# dorbell.net
KiCad netlist of a schematic drawn in EAGLE
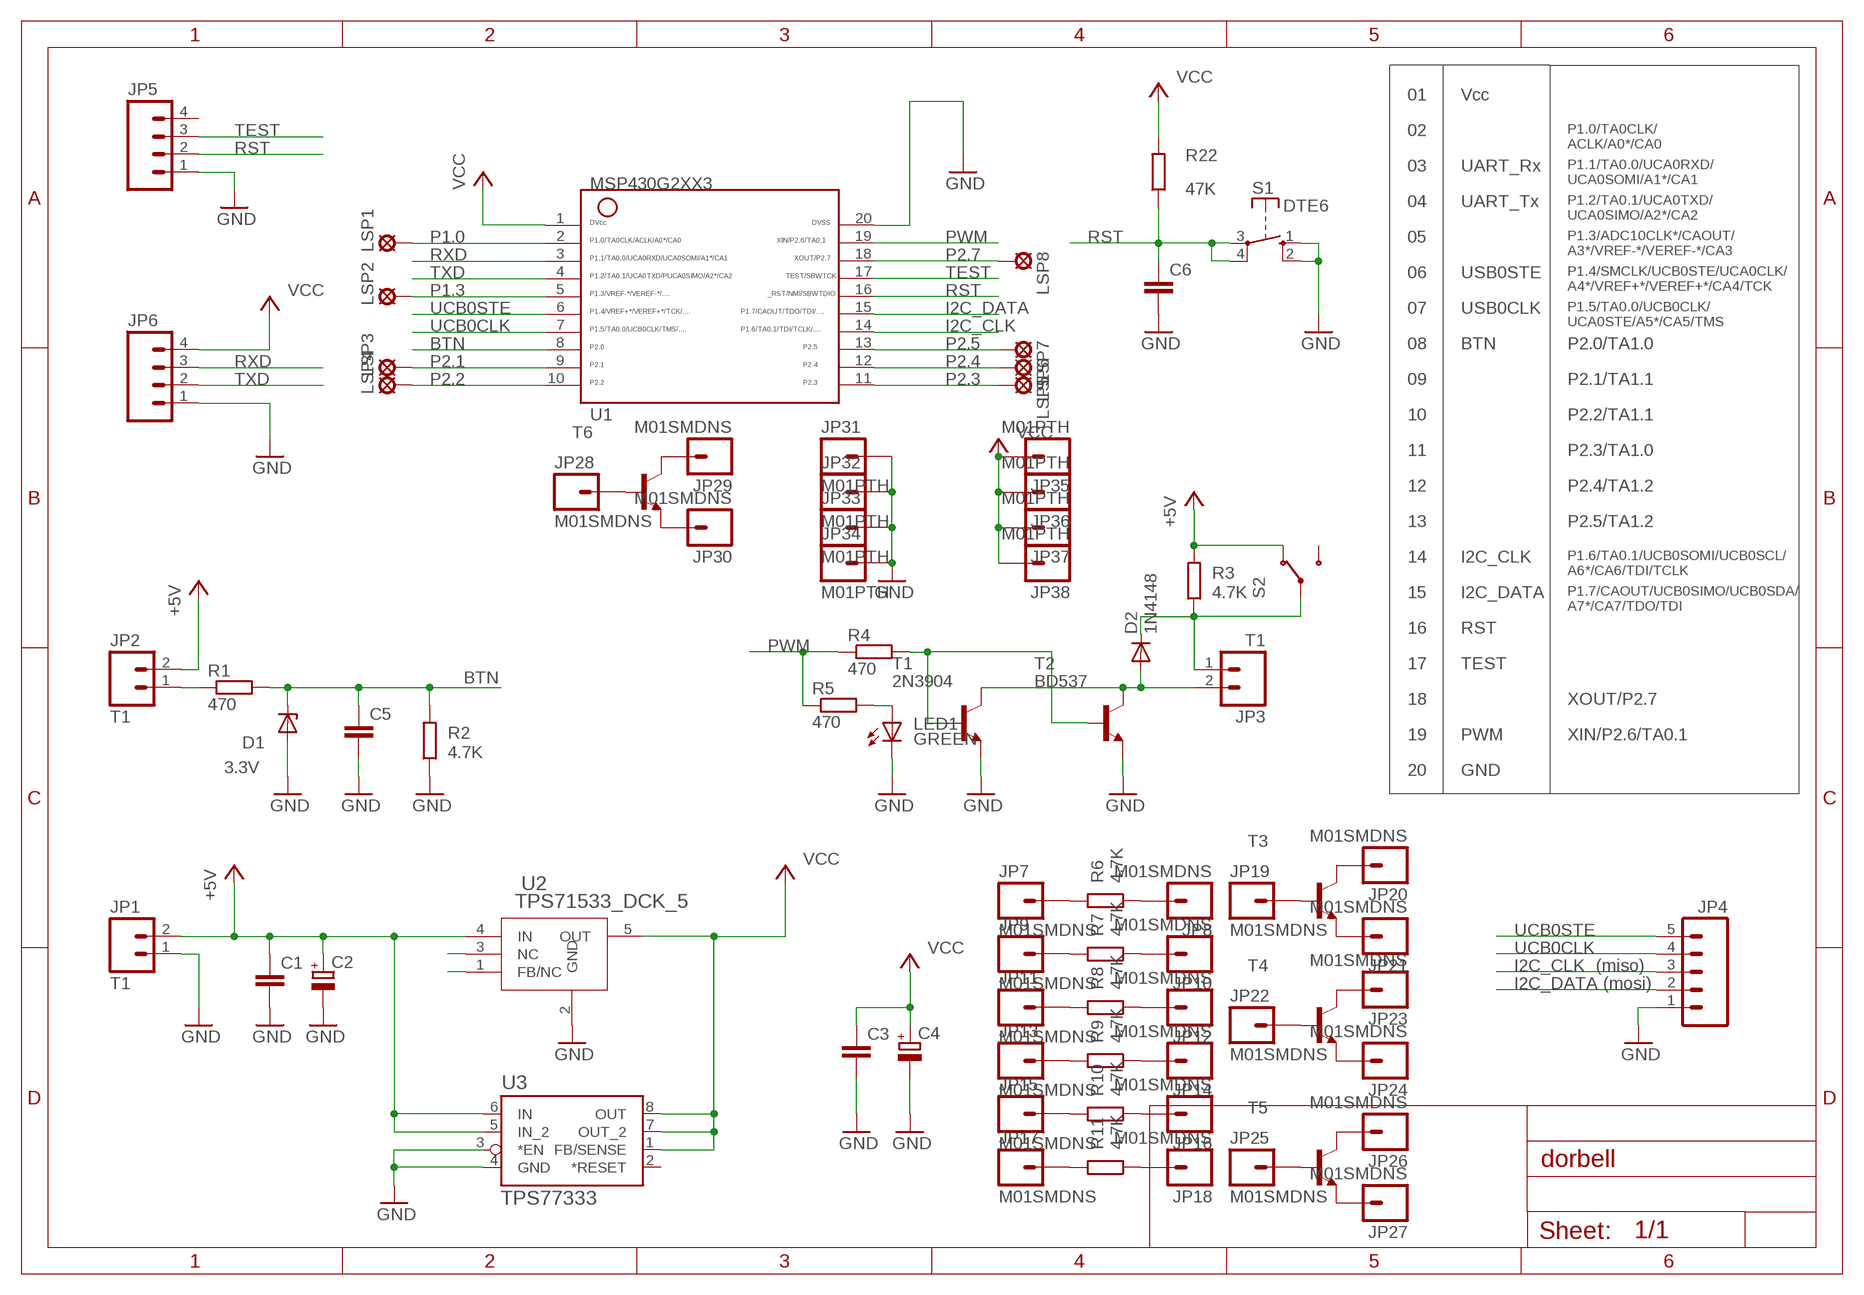
[diagram p0: schematic, sheet 1]

(export (version "E")
  (design (tool "Eeschema 10.0.6"))
  (components
    (comp (ref "C1")
      (value "C-EUC0805")
      (footprint "eagle-import:C0805")
      (libsource (lib "eagle-import") (part "C-EUC0805"))
    )
    (comp (ref "C2")
      (value "CPOL-EUE2.5-7")
      (footprint "eagle-import:E2,5-7")
      (libsource (lib "eagle-import") (part "CPOL-EUE2.5-7"))
    )
    (comp (ref "C3")
      (value "C-EUC0805")
      (footprint "eagle-import:C0805")
      (libsource (lib "eagle-import") (part "C-EUC0805"))
    )
    (comp (ref "C4")
      (value "CPOL-EUE2.5-7")
      (footprint "eagle-import:E2,5-7")
      (libsource (lib "eagle-import") (part "CPOL-EUE2.5-7"))
    )
    (comp (ref "C5")
      (value "C-EUC0805")
      (footprint "eagle-import:C0805")
      (libsource (lib "eagle-import") (part "C-EUC0805"))
    )
    (comp (ref "C6")
      (value "C-EUC0805")
      (footprint "eagle-import:C0805")
      (libsource (lib "eagle-import") (part "C-EUC0805"))
    )
    (comp (ref "D1")
      (value "3.3V")
      (footprint "eagle-import:ZDIO-2.5")
      (libsource (lib "eagle-import") (part "ZENER-DIODEZD-2.5"))
    )
    (comp (ref "D2")
      (value "1N4148")
      (footprint "eagle-import:SOD123")
      (libsource (lib "eagle-import") (part "DIODE-SOD123"))
    )
    (comp (ref "JP1")
      (value "T1")
      (footprint "eagle-import:SCREWTERMINAL-5MM-2")
      (libsource (lib "eagle-import") (part "M025MM"))
    )
    (comp (ref "JP2")
      (value "T1")
      (footprint "eagle-import:SCREWTERMINAL-5MM-2")
      (libsource (lib "eagle-import") (part "M025MM"))
    )
    (comp (ref "JP3")
      (value "T1")
      (footprint "eagle-import:SCREWTERMINAL-5MM-2")
      (libsource (lib "eagle-import") (part "M025MM"))
    )
    (comp (ref "JP4")
      (value "M05PTH")
      (footprint "eagle-import:1X05")
      (libsource (lib "eagle-import") (part "M05PTH"))
    )
    (comp (ref "JP5")
      (value "M04PTH")
      (footprint "eagle-import:1X04")
      (libsource (lib "eagle-import") (part "M04PTH"))
    )
    (comp (ref "JP6")
      (value "M04PTH")
      (footprint "eagle-import:1X04")
      (libsource (lib "eagle-import") (part "M04PTH"))
    )
    (comp (ref "JP7")
      (value "M01SMDNS")
      (footprint "eagle-import:1X01NS")
      (libsource (lib "eagle-import") (part "M01SMDNS"))
    )
    (comp (ref "JP8")
      (value "M01SMDNS")
      (footprint "eagle-import:1X01NS")
      (libsource (lib "eagle-import") (part "M01SMDNS"))
    )
    (comp (ref "JP9")
      (value "M01SMDNS")
      (footprint "eagle-import:1X01NS")
      (libsource (lib "eagle-import") (part "M01SMDNS"))
    )
    (comp (ref "JP10")
      (value "M01SMDNS")
      (footprint "eagle-import:1X01NS")
      (libsource (lib "eagle-import") (part "M01SMDNS"))
    )
    (comp (ref "JP11")
      (value "M01SMDNS")
      (footprint "eagle-import:1X01NS")
      (libsource (lib "eagle-import") (part "M01SMDNS"))
    )
    (comp (ref "JP12")
      (value "M01SMDNS")
      (footprint "eagle-import:1X01NS")
      (libsource (lib "eagle-import") (part "M01SMDNS"))
    )
    (comp (ref "JP13")
      (value "M01SMDNS")
      (footprint "eagle-import:1X01NS")
      (libsource (lib "eagle-import") (part "M01SMDNS"))
    )
    (comp (ref "JP14")
      (value "M01SMDNS")
      (footprint "eagle-import:1X01NS")
      (libsource (lib "eagle-import") (part "M01SMDNS"))
    )
    (comp (ref "JP15")
      (value "M01SMDNS")
      (footprint "eagle-import:1X01NS")
      (libsource (lib "eagle-import") (part "M01SMDNS"))
    )
    (comp (ref "JP16")
      (value "M01SMDNS")
      (footprint "eagle-import:1X01NS")
      (libsource (lib "eagle-import") (part "M01SMDNS"))
    )
    (comp (ref "JP17")
      (value "M01SMDNS")
      (footprint "eagle-import:1X01NS")
      (libsource (lib "eagle-import") (part "M01SMDNS"))
    )
    (comp (ref "JP18")
      (value "M01SMDNS")
      (footprint "eagle-import:1X01NS")
      (libsource (lib "eagle-import") (part "M01SMDNS"))
    )
    (comp (ref "JP19")
      (value "M01SMDNS")
      (footprint "eagle-import:1X01NS")
      (libsource (lib "eagle-import") (part "M01SMDNS"))
    )
    (comp (ref "JP20")
      (value "M01SMDNS")
      (footprint "eagle-import:1X01NS")
      (libsource (lib "eagle-import") (part "M01SMDNS"))
    )
    (comp (ref "JP21")
      (value "M01SMDNS")
      (footprint "eagle-import:1X01NS")
      (libsource (lib "eagle-import") (part "M01SMDNS"))
    )
    (comp (ref "JP22")
      (value "M01SMDNS")
      (footprint "eagle-import:1X01NS")
      (libsource (lib "eagle-import") (part "M01SMDNS"))
    )
    (comp (ref "JP23")
      (value "M01SMDNS")
      (footprint "eagle-import:1X01NS")
      (libsource (lib "eagle-import") (part "M01SMDNS"))
    )
    (comp (ref "JP24")
      (value "M01SMDNS")
      (footprint "eagle-import:1X01NS")
      (libsource (lib "eagle-import") (part "M01SMDNS"))
    )
    (comp (ref "JP25")
      (value "M01SMDNS")
      (footprint "eagle-import:1X01NS")
      (libsource (lib "eagle-import") (part "M01SMDNS"))
    )
    (comp (ref "JP26")
      (value "M01SMDNS")
      (footprint "eagle-import:1X01NS")
      (libsource (lib "eagle-import") (part "M01SMDNS"))
    )
    (comp (ref "JP27")
      (value "M01SMDNS")
      (footprint "eagle-import:1X01NS")
      (libsource (lib "eagle-import") (part "M01SMDNS"))
    )
    (comp (ref "JP28")
      (value "M01SMDNS")
      (footprint "eagle-import:1X01NS")
      (libsource (lib "eagle-import") (part "M01SMDNS"))
    )
    (comp (ref "JP29")
      (value "M01SMDNS")
      (footprint "eagle-import:1X01NS")
      (libsource (lib "eagle-import") (part "M01SMDNS"))
    )
    (comp (ref "JP30")
      (value "M01SMDNS")
      (footprint "eagle-import:1X01NS")
      (libsource (lib "eagle-import") (part "M01SMDNS"))
    )
    (comp (ref "JP31")
      (value "M01PTH")
      (footprint "eagle-import:1X01")
      (libsource (lib "eagle-import") (part "SparkFun-Connectors_M01PTH"))
    )
    (comp (ref "JP32")
      (value "M01PTH")
      (footprint "eagle-import:1X01")
      (libsource (lib "eagle-import") (part "SparkFun-Connectors_M01PTH"))
    )
    (comp (ref "JP33")
      (value "M01PTH")
      (footprint "eagle-import:1X01")
      (libsource (lib "eagle-import") (part "SparkFun-Connectors_M01PTH"))
    )
    (comp (ref "JP34")
      (value "M01PTH")
      (footprint "eagle-import:1X01")
      (libsource (lib "eagle-import") (part "SparkFun-Connectors_M01PTH"))
    )
    (comp (ref "JP35")
      (value "M01PTH")
      (footprint "eagle-import:1X01")
      (libsource (lib "eagle-import") (part "SparkFun-Connectors_M01PTH"))
    )
    (comp (ref "JP36")
      (value "M01PTH")
      (footprint "eagle-import:1X01")
      (libsource (lib "eagle-import") (part "SparkFun-Connectors_M01PTH"))
    )
    (comp (ref "JP37")
      (value "M01PTH")
      (footprint "eagle-import:1X01")
      (libsource (lib "eagle-import") (part "SparkFun-Connectors_M01PTH"))
    )
    (comp (ref "JP38")
      (value "M01PTH")
      (footprint "eagle-import:1X01")
      (libsource (lib "eagle-import") (part "SparkFun-Connectors_M01PTH"))
    )
    (comp (ref "LED1")
      (value "GREEN")
      (footprint "eagle-import:CHIP-LED0805")
      (libsource (lib "eagle-import") (part "LEDCHIP-LED0805"))
    )
    (comp (ref "LSP1")
      (value "LSP10")
      (footprint "eagle-import:LSP10")
      (libsource (lib "eagle-import") (part "LSP10"))
    )
    (comp (ref "LSP2")
      (value "LSP10")
      (footprint "eagle-import:LSP10")
      (libsource (lib "eagle-import") (part "LSP10"))
    )
    (comp (ref "LSP3")
      (value "LSP10")
      (footprint "eagle-import:LSP10")
      (libsource (lib "eagle-import") (part "LSP10"))
    )
    (comp (ref "LSP4")
      (value "LSP10")
      (footprint "eagle-import:LSP10")
      (libsource (lib "eagle-import") (part "LSP10"))
    )
    (comp (ref "LSP5")
      (value "LSP10")
      (footprint "eagle-import:LSP10")
      (libsource (lib "eagle-import") (part "LSP10"))
    )
    (comp (ref "LSP6")
      (value "LSP10")
      (footprint "eagle-import:LSP10")
      (libsource (lib "eagle-import") (part "LSP10"))
    )
    (comp (ref "LSP7")
      (value "LSP10")
      (footprint "eagle-import:LSP10")
      (libsource (lib "eagle-import") (part "LSP10"))
    )
    (comp (ref "LSP8")
      (value "LSP10")
      (footprint "eagle-import:LSP10")
      (libsource (lib "eagle-import") (part "LSP10"))
    )
    (comp (ref "R1")
      (value "470")
      (footprint "eagle-import:R0805")
      (libsource (lib "eagle-import") (part "R-EU_R0805"))
    )
    (comp (ref "R2")
      (value "4.7K")
      (footprint "eagle-import:R0805")
      (libsource (lib "eagle-import") (part "R-EU_R0805"))
    )
    (comp (ref "R3")
      (value "4.7K")
      (footprint "eagle-import:0207_2V")
      (libsource (lib "eagle-import") (part "R-EU_0207/2V"))
    )
    (comp (ref "R4")
      (value "470")
      (footprint "eagle-import:R0805")
      (libsource (lib "eagle-import") (part "R-EU_R0805"))
    )
    (comp (ref "R5")
      (value "470")
      (footprint "eagle-import:R0805")
      (libsource (lib "eagle-import") (part "R-EU_R0805"))
    )
    (comp (ref "R6")
      (value "4.7K")
      (footprint "eagle-import:R0805")
      (libsource (lib "eagle-import") (part "R-EU_R0805"))
    )
    (comp (ref "R7")
      (value "4.7K")
      (footprint "eagle-import:R0805")
      (libsource (lib "eagle-import") (part "R-EU_R0805"))
    )
    (comp (ref "R8")
      (value "4.7K")
      (footprint "eagle-import:R0805")
      (libsource (lib "eagle-import") (part "R-EU_R0805"))
    )
    (comp (ref "R9")
      (value "4.7K")
      (footprint "eagle-import:R0805")
      (libsource (lib "eagle-import") (part "R-EU_R0805"))
    )
    (comp (ref "R10")
      (value "4.7K")
      (footprint "eagle-import:R0805")
      (libsource (lib "eagle-import") (part "R-EU_R0805"))
    )
    (comp (ref "R11")
      (value "4.7K")
      (footprint "eagle-import:R0805")
      (libsource (lib "eagle-import") (part "R-EU_R0805"))
    )
    (comp (ref "R22")
      (value "47K")
      (footprint "eagle-import:R0805")
      (libsource (lib "eagle-import") (part "R-EU_R0805"))
    )
    (comp (ref "S1")
      (value "DTE6")
      (footprint "eagle-import:DTE6")
      (libsource (lib "eagle-import") (part "DTE6"))
    )
    (comp (ref "S2")
      (value "SWITCH_2DIR")
      (footprint "eagle-import:SWITCH_SLIDE")
      (libsource (lib "eagle-import") (part "SWITCH_2DIR"))
    )
    (comp (ref "T1")
      (value "2N3904")
      (footprint "eagle-import:TO92")
      (libsource (lib "eagle-import") (part "2N3904"))
    )
    (comp (ref "T2")
      (value "BD537")
      (footprint "eagle-import:TO220V")
      (libsource (lib "eagle-import") (part "-NPN-TO220V"))
    )
    (comp (ref "T3")
      (value "MMBT3904LT1-NPN-SOT23-BEC")
      (footprint "eagle-import:SOT23-BEC")
      (libsource (lib "eagle-import") (part "-NPN-SOT23-BECMMBT3904LT1"))
    )
    (comp (ref "T4")
      (value "MMBT3904LT1-NPN-SOT23-BEC")
      (footprint "eagle-import:SOT23-BEC")
      (libsource (lib "eagle-import") (part "-NPN-SOT23-BECMMBT3904LT1"))
    )
    (comp (ref "T5")
      (value "MMBT3904LT1-NPN-SOT23-BEC")
      (footprint "eagle-import:SOT23-BEC")
      (libsource (lib "eagle-import") (part "-NPN-SOT23-BECMMBT3904LT1"))
    )
    (comp (ref "T6")
      (value "-NPN-TO92-E1")
      (footprint "eagle-import:TO92-E1")
      (libsource (lib "eagle-import") (part "-NPN-TO92-E1"))
    )
    (comp (ref "U1")
      (value "G2XX3---PW20")
      (footprint "eagle-import:PW20")
      (libsource (lib "eagle-import") (part "G2XX3---PW20"))
    )
    (comp (ref "U2")
      (value "TPS71533_DCK_5")
      (footprint "eagle-import:DCK5")
      (fields
        (field (name "GENERIC_PART_NUMBER") "TPS71533")
        (field (name "MANUFACTURER") "Texas Instruments")
        (field (name "MANUFACTURER_PART_NUMBER") "tps71533_dck_5")
      )
      (libsource (lib "eagle-import") (part "TPS71533_DCK_5"))
    )
    (comp (ref "U3")
      (value "TPS77333")
      (footprint "eagle-import:DGK8")
      (libsource (lib "eagle-import") (part "TPS77333"))
    )
  )
  (nets
    (net (code "1") (name "+5V") (class "Default")
      (node (ref "C1") (pin "1") (pinfunction "1_1") (pintype "passive"))
      (node (ref "C2") (pin "+") (pinfunction "+_+") (pintype "passive"))
      (node (ref "JP1") (pin "2") (pinfunction "2_2") (pintype "passive"))
      (node (ref "JP2") (pin "2") (pinfunction "2_2") (pintype "passive"))
      (node (ref "R3") (pin "2") (pinfunction "2_2") (pintype "passive"))
      (node (ref "S2") (pin "P$1") (pinfunction "P$1_P$1") (pintype "bidirectional"))
      (node (ref "U2") (pin "4") (pinfunction "IN_4") (pintype "input"))
      (node (ref "U3") (pin "5") (pinfunction "IN_2_5") (pintype "input"))
      (node (ref "U3") (pin "6") (pinfunction "IN_6") (pintype "input"))
    )
    (net (code "2") (name "/BTN") (class "Default")
      (node (ref "C5") (pin "1") (pinfunction "1_1") (pintype "passive"))
      (node (ref "D1") (pin "C") (pinfunction "C_C") (pintype "passive"))
      (node (ref "R1") (pin "2") (pinfunction "2_2") (pintype "passive"))
      (node (ref "R2") (pin "2") (pinfunction "2_2") (pintype "passive"))
      (node (ref "U1") (pin "8") (pinfunction "8_8") (pintype "bidirectional"))
    )
    (net (code "3") (name "/I2C_CLK") (class "Default")
      (node (ref "JP4") (pin "3") (pinfunction "3_3") (pintype "passive"))
      (node (ref "U1") (pin "14") (pinfunction "14_14") (pintype "bidirectional"))
    )
    (net (code "4") (name "/I2C_DATA") (class "Default")
      (node (ref "JP4") (pin "2") (pinfunction "2_2") (pintype "passive"))
      (node (ref "U1") (pin "15") (pinfunction "15_15") (pintype "bidirectional"))
    )
    (net (code "5") (name "/P1.0") (class "Default")
      (node (ref "LSP1") (pin "MP") (pinfunction "MP_MP") (pintype "passive"))
      (node (ref "U1") (pin "2") (pinfunction "2_2") (pintype "bidirectional"))
    )
    (net (code "6") (name "/P1.3") (class "Default")
      (node (ref "LSP2") (pin "MP") (pinfunction "MP_MP") (pintype "passive"))
      (node (ref "U1") (pin "5") (pinfunction "5_5") (pintype "bidirectional"))
    )
    (net (code "7") (name "/P2.1") (class "Default")
      (node (ref "LSP3") (pin "MP") (pinfunction "MP_MP") (pintype "passive"))
      (node (ref "U1") (pin "9") (pinfunction "9_9") (pintype "bidirectional"))
    )
    (net (code "8") (name "/P2.2") (class "Default")
      (node (ref "LSP4") (pin "MP") (pinfunction "MP_MP") (pintype "passive"))
      (node (ref "U1") (pin "10") (pinfunction "10_10") (pintype "bidirectional"))
    )
    (net (code "9") (name "/P2.3") (class "Default")
      (node (ref "LSP5") (pin "MP") (pinfunction "MP_MP") (pintype "passive"))
      (node (ref "U1") (pin "11") (pinfunction "11_11") (pintype "bidirectional"))
    )
    (net (code "10") (name "/P2.4") (class "Default")
      (node (ref "LSP6") (pin "MP") (pinfunction "MP_MP") (pintype "passive"))
      (node (ref "U1") (pin "12") (pinfunction "12_12") (pintype "bidirectional"))
    )
    (net (code "11") (name "/P2.5") (class "Default")
      (node (ref "LSP7") (pin "MP") (pinfunction "MP_MP") (pintype "passive"))
      (node (ref "U1") (pin "13") (pinfunction "13_13") (pintype "bidirectional"))
    )
    (net (code "12") (name "/P2.7") (class "Default")
      (node (ref "LSP8") (pin "MP") (pinfunction "MP_MP") (pintype "passive"))
      (node (ref "U1") (pin "18") (pinfunction "18_18") (pintype "bidirectional"))
    )
    (net (code "13") (name "/PWM") (class "Default")
      (node (ref "R4") (pin "1") (pinfunction "1_1") (pintype "passive"))
      (node (ref "R5") (pin "1") (pinfunction "1_1") (pintype "passive"))
      (node (ref "U1") (pin "19") (pinfunction "19_19") (pintype "bidirectional"))
    )
    (net (code "14") (name "/RST") (class "Default")
      (node (ref "C6") (pin "1") (pinfunction "1_1") (pintype "passive"))
      (node (ref "JP5") (pin "2") (pinfunction "2_2") (pintype "passive"))
      (node (ref "R22") (pin "1") (pinfunction "1_1") (pintype "passive"))
      (node (ref "S1") (pin "3") (pinfunction "P_3") (pintype "passive"))
      (node (ref "S1") (pin "4") (pinfunction "P_4") (pintype "passive"))
      (node (ref "U1") (pin "16") (pinfunction "16_16") (pintype "bidirectional"))
    )
    (net (code "15") (name "/RXD") (class "Default")
      (node (ref "JP6") (pin "3") (pinfunction "3_3") (pintype "passive"))
      (node (ref "U1") (pin "3") (pinfunction "3_3") (pintype "bidirectional"))
    )
    (net (code "16") (name "/TEST") (class "Default")
      (node (ref "JP5") (pin "3") (pinfunction "3_3") (pintype "passive"))
      (node (ref "U1") (pin "17") (pinfunction "17_17") (pintype "bidirectional"))
    )
    (net (code "17") (name "/TXD") (class "Default")
      (node (ref "JP6") (pin "2") (pinfunction "2_2") (pintype "passive"))
      (node (ref "U1") (pin "4") (pinfunction "4_4") (pintype "bidirectional"))
    )
    (net (code "18") (name "/UCB0CLK") (class "Default")
      (node (ref "JP4") (pin "4") (pinfunction "4_4") (pintype "passive"))
      (node (ref "U1") (pin "7") (pinfunction "7_7") (pintype "bidirectional"))
    )
    (net (code "19") (name "/UCB0STE") (class "Default")
      (node (ref "JP4") (pin "5") (pinfunction "5_5") (pintype "passive"))
      (node (ref "U1") (pin "6") (pinfunction "6_6") (pintype "bidirectional"))
    )
    (net (code "20") (name "GND") (class "Default")
      (node (ref "C1") (pin "2") (pinfunction "2_2") (pintype "passive"))
      (node (ref "C2") (pin "-") (pinfunction "-_-") (pintype "passive"))
      (node (ref "C3") (pin "2") (pinfunction "2_2") (pintype "passive"))
      (node (ref "C4") (pin "-") (pinfunction "-_-") (pintype "passive"))
      (node (ref "C5") (pin "2") (pinfunction "2_2") (pintype "passive"))
      (node (ref "C6") (pin "2") (pinfunction "2_2") (pintype "passive"))
      (node (ref "D1") (pin "A") (pinfunction "A_A") (pintype "passive"))
      (node (ref "JP1") (pin "1") (pinfunction "1_1") (pintype "passive"))
      (node (ref "JP31") (pin "1") (pinfunction "1_1") (pintype "passive"))
      (node (ref "JP32") (pin "1") (pinfunction "1_1") (pintype "passive"))
      (node (ref "JP33") (pin "1") (pinfunction "1_1") (pintype "passive"))
      (node (ref "JP34") (pin "1") (pinfunction "1_1") (pintype "passive"))
      (node (ref "JP4") (pin "1") (pinfunction "1_1") (pintype "passive"))
      (node (ref "JP5") (pin "1") (pinfunction "1_1") (pintype "passive"))
      (node (ref "JP6") (pin "1") (pinfunction "1_1") (pintype "passive"))
      (node (ref "LED1") (pin "C") (pinfunction "C_C") (pintype "passive"))
      (node (ref "R2") (pin "1") (pinfunction "1_1") (pintype "passive"))
      (node (ref "S1") (pin "1") (pinfunction "S_1") (pintype "passive"))
      (node (ref "S1") (pin "2") (pinfunction "S_2") (pintype "passive"))
      (node (ref "T1") (pin "3") (pinfunction "E_3") (pintype "passive"))
      (node (ref "T2") (pin "3") (pinfunction "E_3") (pintype "passive"))
      (node (ref "U1") (pin "20") (pinfunction "20_20") (pintype "bidirectional"))
      (node (ref "U2") (pin "2") (pinfunction "GND_2") (pintype "power_in"))
      (node (ref "U3") (pin "3") (pinfunction "*EN_3") (pintype "input"))
      (node (ref "U3") (pin "4") (pinfunction "GND_4") (pintype "power_in"))
    )
    (net (code "21") (name "Net-(D2-PadC)") (class "Default")
      (node (ref "D2") (pin "C") (pinfunction "C_C") (pintype "passive"))
      (node (ref "JP3") (pin "1") (pinfunction "1_1") (pintype "passive"))
      (node (ref "R3") (pin "1") (pinfunction "1_1") (pintype "passive"))
      (node (ref "S2") (pin "P$2") (pinfunction "P$2_P$2") (pintype "bidirectional"))
    )
    (net (code "22") (name "Net-(JP2-Pad1)") (class "Default")
      (node (ref "JP2") (pin "1") (pinfunction "1_1") (pintype "passive"))
      (node (ref "R1") (pin "1") (pinfunction "1_1") (pintype "passive"))
    )
    (net (code "23") (name "Net-(JP7-Pad1)") (class "Default")
      (node (ref "JP7") (pin "1") (pinfunction "1_1") (pintype "passive"))
      (node (ref "R6") (pin "2") (pinfunction "2_2") (pintype "passive"))
    )
    (net (code "24") (name "Net-(JP8-Pad1)") (class "Default")
      (node (ref "JP8") (pin "1") (pinfunction "1_1") (pintype "passive"))
      (node (ref "R6") (pin "1") (pinfunction "1_1") (pintype "passive"))
    )
    (net (code "25") (name "Net-(JP9-Pad1)") (class "Default")
      (node (ref "JP9") (pin "1") (pinfunction "1_1") (pintype "passive"))
      (node (ref "R7") (pin "2") (pinfunction "2_2") (pintype "passive"))
    )
    (net (code "26") (name "Net-(JP10-Pad1)") (class "Default")
      (node (ref "JP10") (pin "1") (pinfunction "1_1") (pintype "passive"))
      (node (ref "R7") (pin "1") (pinfunction "1_1") (pintype "passive"))
    )
    (net (code "27") (name "Net-(JP11-Pad1)") (class "Default")
      (node (ref "JP11") (pin "1") (pinfunction "1_1") (pintype "passive"))
      (node (ref "R8") (pin "2") (pinfunction "2_2") (pintype "passive"))
    )
    (net (code "28") (name "Net-(JP12-Pad1)") (class "Default")
      (node (ref "JP12") (pin "1") (pinfunction "1_1") (pintype "passive"))
      (node (ref "R8") (pin "1") (pinfunction "1_1") (pintype "passive"))
    )
    (net (code "29") (name "Net-(JP13-Pad1)") (class "Default")
      (node (ref "JP13") (pin "1") (pinfunction "1_1") (pintype "passive"))
      (node (ref "R9") (pin "2") (pinfunction "2_2") (pintype "passive"))
    )
    (net (code "30") (name "Net-(JP14-Pad1)") (class "Default")
      (node (ref "JP14") (pin "1") (pinfunction "1_1") (pintype "passive"))
      (node (ref "R9") (pin "1") (pinfunction "1_1") (pintype "passive"))
    )
    (net (code "31") (name "Net-(JP15-Pad1)") (class "Default")
      (node (ref "JP15") (pin "1") (pinfunction "1_1") (pintype "passive"))
      (node (ref "R10") (pin "2") (pinfunction "2_2") (pintype "passive"))
    )
    (net (code "32") (name "Net-(JP16-Pad1)") (class "Default")
      (node (ref "JP16") (pin "1") (pinfunction "1_1") (pintype "passive"))
      (node (ref "R10") (pin "1") (pinfunction "1_1") (pintype "passive"))
    )
    (net (code "33") (name "Net-(JP17-Pad1)") (class "Default")
      (node (ref "JP17") (pin "1") (pinfunction "1_1") (pintype "passive"))
      (node (ref "R11") (pin "2") (pinfunction "2_2") (pintype "passive"))
    )
    (net (code "34") (name "Net-(JP18-Pad1)") (class "Default")
      (node (ref "JP18") (pin "1") (pinfunction "1_1") (pintype "passive"))
      (node (ref "R11") (pin "1") (pinfunction "1_1") (pintype "passive"))
    )
    (net (code "35") (name "Net-(JP19-Pad1)") (class "Default")
      (node (ref "JP19") (pin "1") (pinfunction "1_1") (pintype "passive"))
      (node (ref "T3") (pin "B") (pinfunction "B_B") (pintype "passive"))
    )
    (net (code "36") (name "Net-(JP20-Pad1)") (class "Default")
      (node (ref "JP20") (pin "1") (pinfunction "1_1") (pintype "passive"))
      (node (ref "T3") (pin "C") (pinfunction "C_C") (pintype "passive"))
    )
    (net (code "37") (name "Net-(JP21-Pad1)") (class "Default")
      (node (ref "JP21") (pin "1") (pinfunction "1_1") (pintype "passive"))
      (node (ref "T3") (pin "E") (pinfunction "E_E") (pintype "passive"))
    )
    (net (code "38") (name "Net-(JP22-Pad1)") (class "Default")
      (node (ref "JP22") (pin "1") (pinfunction "1_1") (pintype "passive"))
      (node (ref "T4") (pin "B") (pinfunction "B_B") (pintype "passive"))
    )
    (net (code "39") (name "Net-(JP23-Pad1)") (class "Default")
      (node (ref "JP23") (pin "1") (pinfunction "1_1") (pintype "passive"))
      (node (ref "T4") (pin "C") (pinfunction "C_C") (pintype "passive"))
    )
    (net (code "40") (name "Net-(JP24-Pad1)") (class "Default")
      (node (ref "JP24") (pin "1") (pinfunction "1_1") (pintype "passive"))
      (node (ref "T4") (pin "E") (pinfunction "E_E") (pintype "passive"))
    )
    (net (code "41") (name "Net-(JP25-Pad1)") (class "Default")
      (node (ref "JP25") (pin "1") (pinfunction "1_1") (pintype "passive"))
      (node (ref "T5") (pin "B") (pinfunction "B_B") (pintype "passive"))
    )
    (net (code "42") (name "Net-(JP26-Pad1)") (class "Default")
      (node (ref "JP26") (pin "1") (pinfunction "1_1") (pintype "passive"))
      (node (ref "T5") (pin "C") (pinfunction "C_C") (pintype "passive"))
    )
    (net (code "43") (name "Net-(JP27-Pad1)") (class "Default")
      (node (ref "JP27") (pin "1") (pinfunction "1_1") (pintype "passive"))
      (node (ref "T5") (pin "E") (pinfunction "E_E") (pintype "passive"))
    )
    (net (code "44") (name "Net-(LED1-PadA)") (class "Default")
      (node (ref "LED1") (pin "A") (pinfunction "A_A") (pintype "passive"))
      (node (ref "R5") (pin "2") (pinfunction "2_2") (pintype "passive"))
    )
    (net (code "45") (name "Net-(T1-B)") (class "Default")
      (node (ref "R4") (pin "2") (pinfunction "2_2") (pintype "passive"))
      (node (ref "T1") (pin "2") (pinfunction "B_2") (pintype "passive"))
      (node (ref "T2") (pin "1") (pinfunction "B_1") (pintype "passive"))
    )
    (net (code "46") (name "Net-(T1-C)") (class "Default")
      (node (ref "D2") (pin "A") (pinfunction "A_A") (pintype "passive"))
      (node (ref "JP3") (pin "2") (pinfunction "2_2") (pintype "passive"))
      (node (ref "T1") (pin "1") (pinfunction "C_1") (pintype "passive"))
      (node (ref "T2") (pin "2") (pinfunction "C_2") (pintype "passive"))
    )
    (net (code "47") (name "Net-(T6-B)") (class "Default")
      (node (ref "JP28") (pin "1") (pinfunction "1_1") (pintype "passive"))
      (node (ref "T6") (pin "2") (pinfunction "B_2") (pintype "passive"))
    )
    (net (code "48") (name "Net-(T6-C)") (class "Default")
      (node (ref "JP29") (pin "1") (pinfunction "1_1") (pintype "passive"))
      (node (ref "T6") (pin "1") (pinfunction "C_1") (pintype "passive"))
    )
    (net (code "49") (name "Net-(T6-E)") (class "Default")
      (node (ref "JP30") (pin "1") (pinfunction "1_1") (pintype "passive"))
      (node (ref "T6") (pin "3") (pinfunction "E_3") (pintype "passive"))
    )
    (net (code "50") (name "VCC") (class "Default")
      (node (ref "C3") (pin "1") (pinfunction "1_1") (pintype "passive"))
      (node (ref "C4") (pin "+") (pinfunction "+_+") (pintype "passive"))
      (node (ref "JP35") (pin "1") (pinfunction "1_1") (pintype "passive"))
      (node (ref "JP36") (pin "1") (pinfunction "1_1") (pintype "passive"))
      (node (ref "JP37") (pin "1") (pinfunction "1_1") (pintype "passive"))
      (node (ref "JP38") (pin "1") (pinfunction "1_1") (pintype "passive"))
      (node (ref "JP6") (pin "4") (pinfunction "4_4") (pintype "passive"))
      (node (ref "R22") (pin "2") (pinfunction "2_2") (pintype "passive"))
      (node (ref "U1") (pin "1") (pinfunction "1_1") (pintype "bidirectional"))
      (node (ref "U2") (pin "5") (pinfunction "OUT_5") (pintype "output"))
      (node (ref "U3") (pin "1") (pinfunction "FB/SENSE_1") (pintype "input"))
      (node (ref "U3") (pin "7") (pinfunction "OUT_2_7") (pintype "output"))
      (node (ref "U3") (pin "8") (pinfunction "OUT_8") (pintype "output"))
    )
    (net (code "51") (name "unconnected-(JP5-Pad4)") (class "Default")
      (node (ref "JP5") (pin "4") (pinfunction "4_4") (pintype "passive"))
    )
    (net (code "52") (name "unconnected-(S2-PadP$3)") (class "Default")
      (node (ref "S2") (pin "P$3") (pinfunction "P$3_P$3") (pintype "bidirectional"))
    )
    (net (code "53") (name "unconnected-(U2-FB{slash}NC-Pad1)") (class "Default")
      (node (ref "U2") (pin "1") (pinfunction "FB/NC_1") (pintype "bidirectional"))
    )
    (net (code "54") (name "unconnected-(U2-NC-Pad3)") (class "Default")
      (node (ref "U2") (pin "3") (pinfunction "NC_3") (pintype "passive"))
    )
    (net (code "55") (name "unconnected-(U3-*RESET-Pad2)") (class "Default")
      (node (ref "U3") (pin "2") (pinfunction "*RESET_2") (pintype "output"))
    )
  )
)
